# Pg16_PSU.net
KiCad netlist of a schematic drawn in Altium Designer
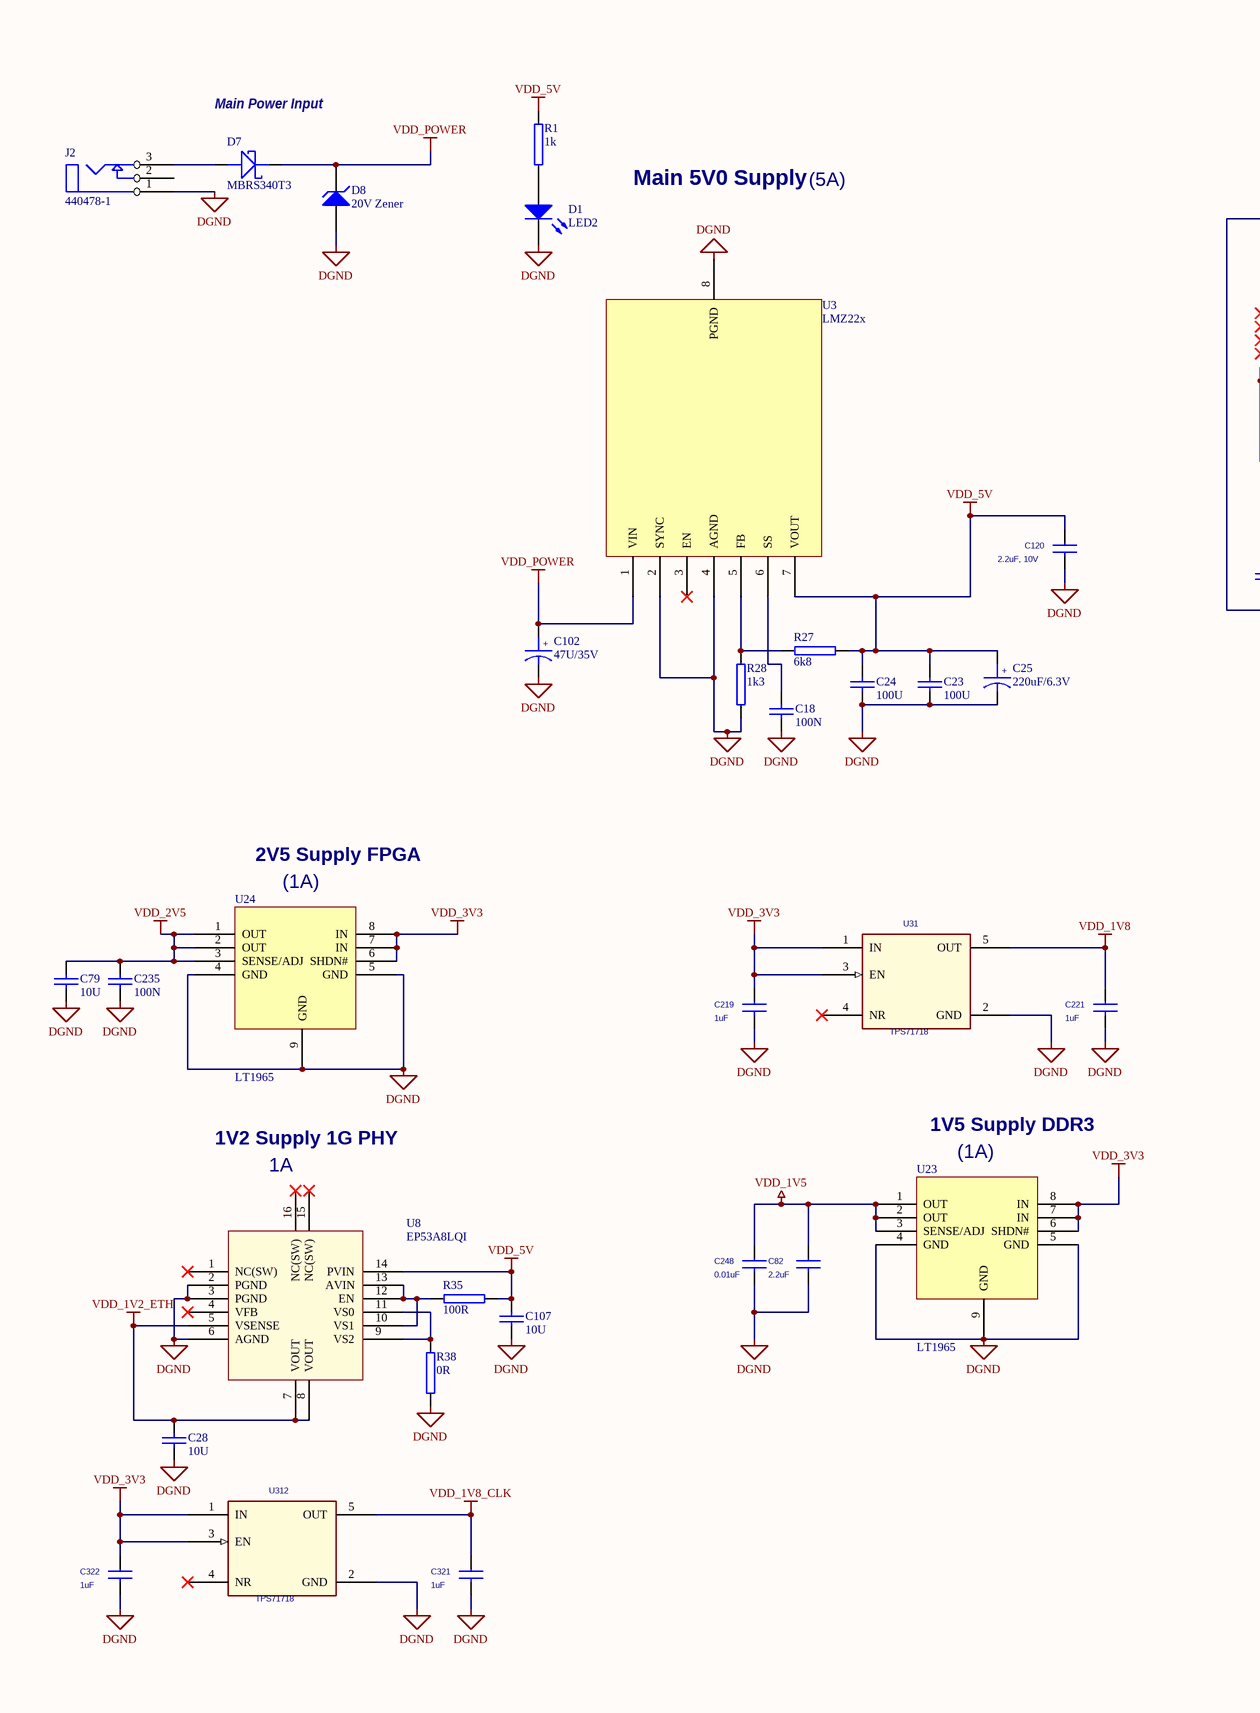
[diagram p0: Pg16_PSU.SchDoc, left]
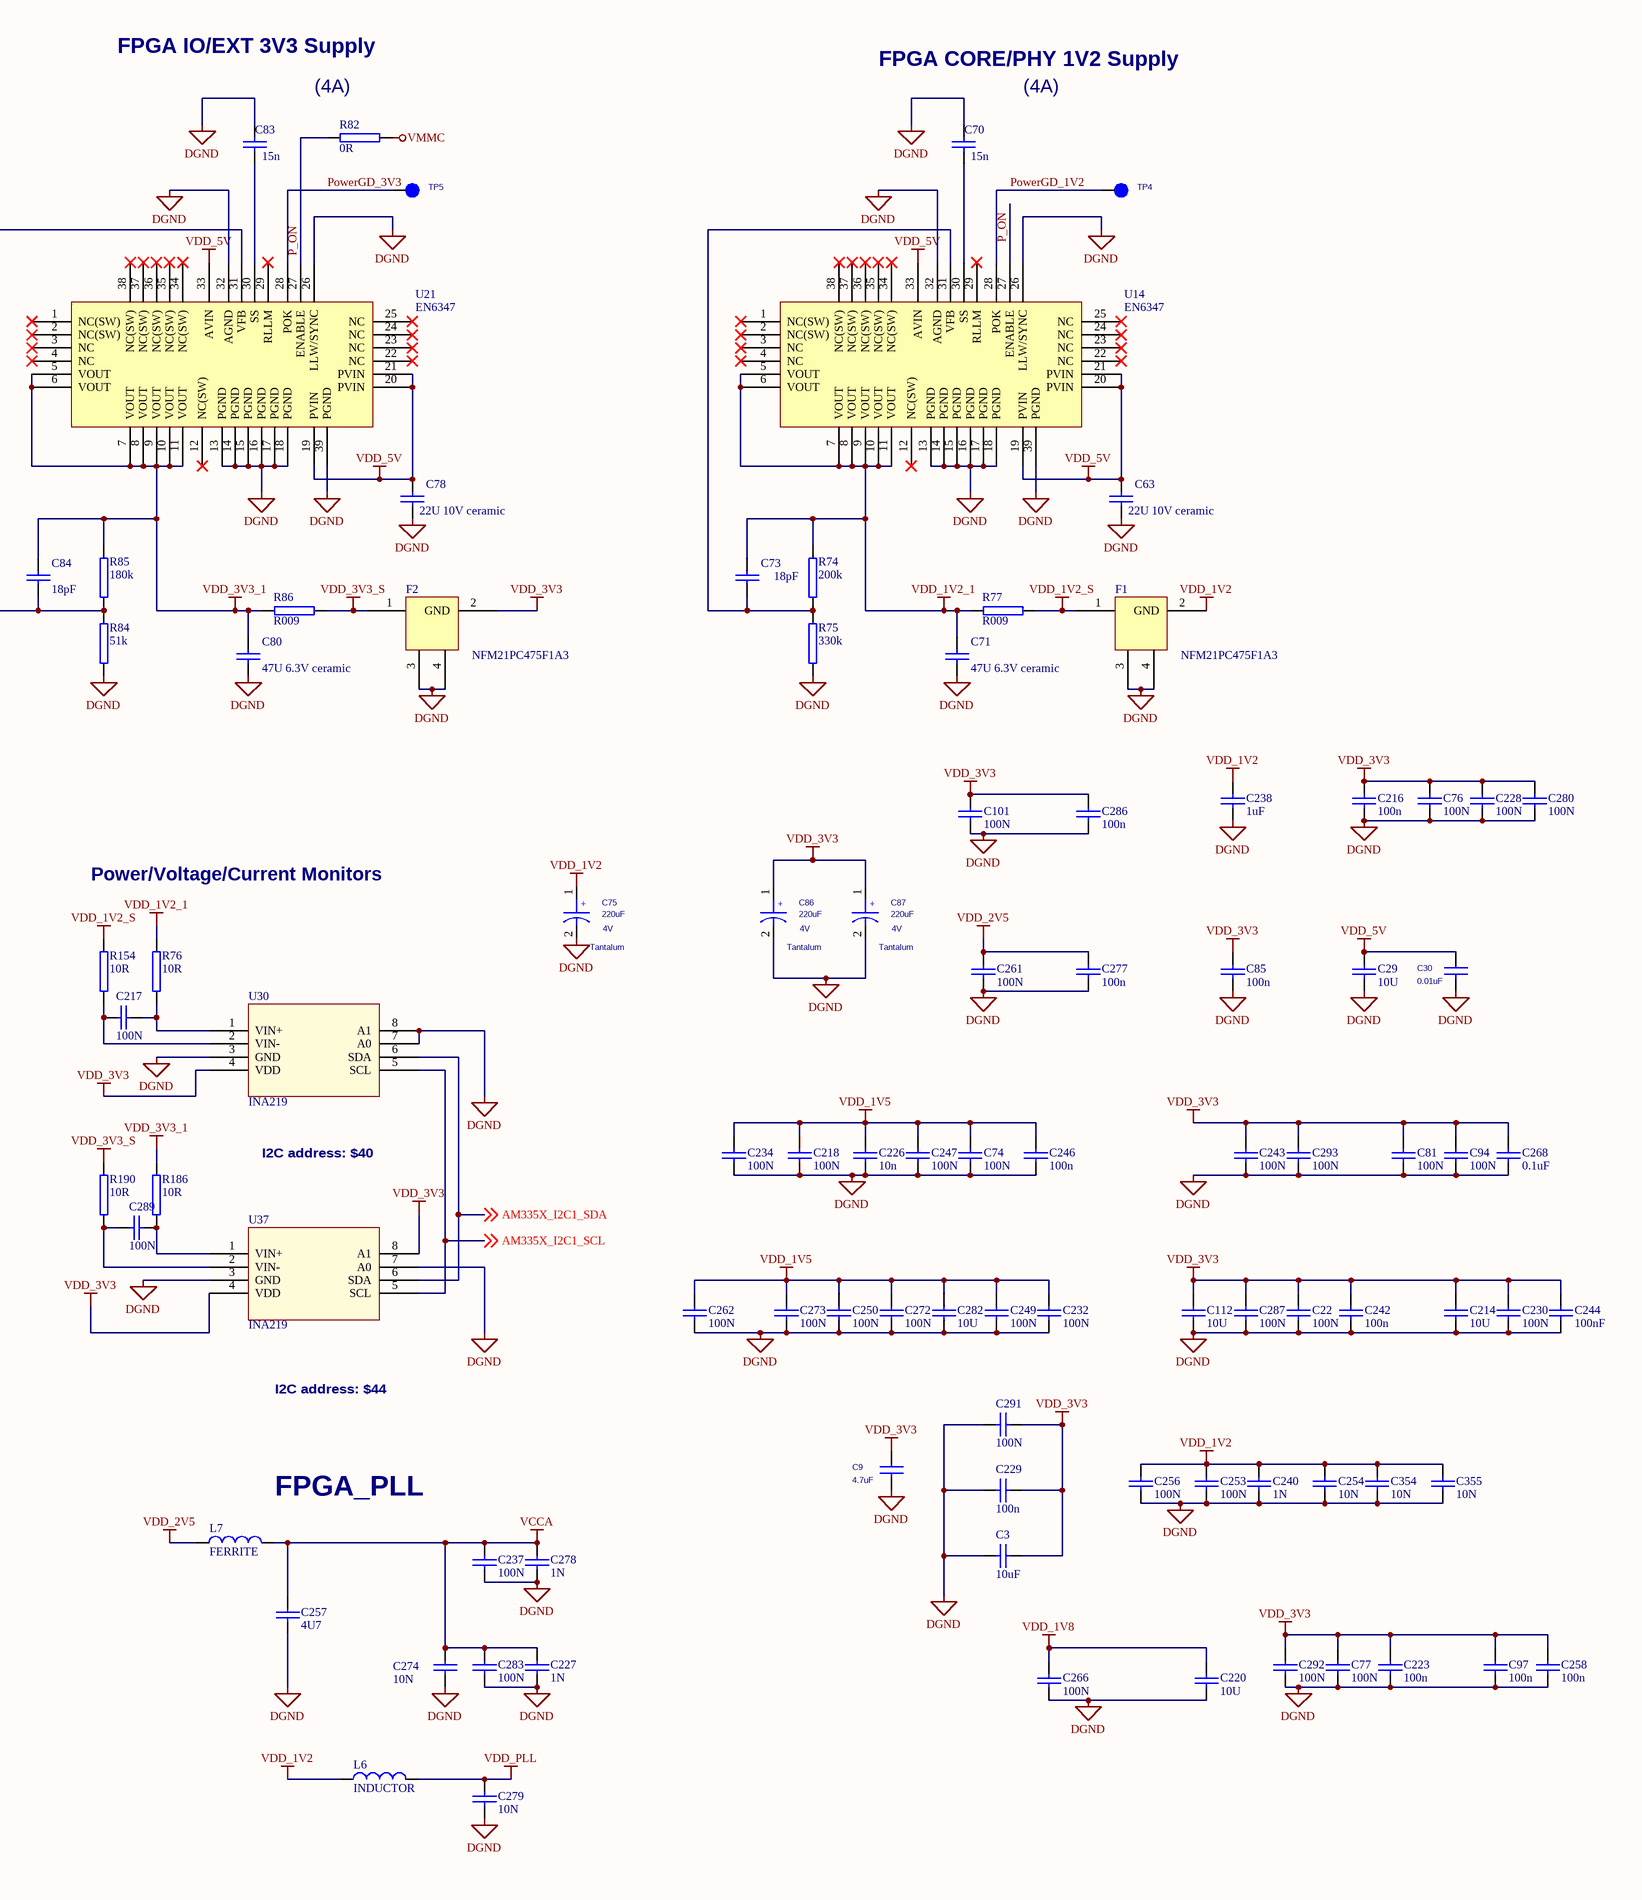
[diagram p1: Pg16_PSU.SchDoc, right]

(export (version "E")
  (design (tool "Eeschema 10.0.6"))
  (components
    (comp (ref "C3")
      (value "10uF")
      (footprint "SC0603")
      (description "NON-POLARISED CAP")
      (libsource (lib "Fireflash_B") (part "CAP"))
    )
    (comp (ref "C9")
      (value "4.7uF")
      (footprint "SM-7351-CAP-0603")
      (fields (field (name "TIINTPARTNUMBER") "1C0103") (field (name "MFR") "Taiyo Yuden"))
      (libsource (lib "*") (part "4.7uFCapacitor16V10%0603"))
    )
    (comp (ref "C18")
      (value "100N")
      (footprint "sc0402")
      (description "NON-POLARISED CAP")
      (libsource (lib "Fireflash_B") (part "CAP"))
    )
    (comp (ref "C22")
      (value "100N")
      (footprint "0603")
      (description "NON-POLARISED CAP")
      (libsource (lib "Fireflash_B") (part "CAP"))
    )
    (comp (ref "C23")
      (value "100U")
      (footprint "1206")
      (description "NON-POLARISED CAP")
      (libsource (lib "Fireflash_B") (part "CAP"))
    )
    (comp (ref "C24")
      (value "100U")
      (footprint "1206")
      (description "NON-POLARISED CAP")
      (libsource (lib "Fireflash_B") (part "CAP"))
    )
    (comp (ref "C25")
      (value "220uF/6.3V")
      (footprint "CASED")
      (description "POLARISED CAPACITOR")
      (libsource (lib "Fireflash_B") (part "CAP POL"))
    )
    (comp (ref "C28")
      (value "10U")
      (footprint "SC0603")
      (description "NON-POLARISED CAP")
      (libsource (lib "Fireflash_B") (part "CAP"))
    )
    (comp (ref "C29")
      (value "10U")
      (footprint "0805")
      (description "NON-POLARISED CAP")
      (libsource (lib "Fireflash_B") (part "CAP"))
    )
    (comp (ref "C30")
      (value "0.01uF")
      (footprint "SM-7351-CAP-0402")
      (fields (field (name "MFR") "Panasonic") (field (name "TIINTPARTNUMBER") "1C0012"))
      (libsource (lib "*") (part "0.01uFCapacitor16V10%0402_Dup1"))
    )
    (comp (ref "C63")
      (value "22U 10V ceramic")
      (footprint "1206")
      (description "NON-POLARISED CAP")
      (libsource (lib "*") (part "CAP"))
    )
    (comp (ref "C70")
      (value "15n")
      (footprint "sc0402")
      (description "NON-POLARISED CAP")
      (libsource (lib "*") (part "CAP"))
    )
    (comp (ref "C71")
      (value "47U 6.3V ceramic")
      (footprint "1206")
      (description "NON-POLARISED CAP")
      (libsource (lib "*") (part "CAP"))
    )
    (comp (ref "C73")
      (value "18pF")
      (footprint "sc0402")
      (description "NON-POLARISED CAP")
      (libsource (lib "*") (part "CAP"))
    )
    (comp (ref "C74")
      (value "100N")
      (footprint "0603")
      (description "NON-POLARISED CAP")
      (libsource (lib "Fireflash_B") (part "CAP"))
    )
    (comp (ref "C75")
      (value "220uF")
      (footprint "1210")
      (description "CAP - TANTALUM, 330UF, 10%, 4V, 700MOHM ESR, 6032-28")
      (fields
        (field (name "WORKING VOLTAGE") "4V")
        (field (name "DIELECTRIC") "Tantalum")
        (field (name "TOLERANCE") "+/-10%")
        (field (name "MANUFACTURER") "Kemet Corporation")
      )
      (libsource (lib "*") (part "CAP_SMD_POL"))
    )
    (comp (ref "C76")
      (value "100N")
      (footprint "sc0402")
      (description "NON-POLARISED CAP")
      (libsource (lib "Fireflash_B") (part "CAP"))
    )
    (comp (ref "C77")
      (value "100N")
      (footprint "0603")
      (description "NON-POLARISED CAP")
      (libsource (lib "Fireflash_B") (part "CAP"))
    )
    (comp (ref "C78")
      (value "22U 10V ceramic")
      (footprint "1206")
      (description "NON-POLARISED CAP")
      (libsource (lib "*") (part "CAP"))
    )
    (comp (ref "C79")
      (value "10U")
      (footprint "sc0603")
      (description "NON-POLARISED CAP")
      (libsource (lib "Fireflash_B") (part "CAP"))
    )
    (comp (ref "C80")
      (value "47U 6.3V ceramic")
      (footprint "1206")
      (description "NON-POLARISED CAP")
      (libsource (lib "*") (part "CAP"))
    )
    (comp (ref "C81")
      (value "100N")
      (footprint "0603")
      (description "NON-POLARISED CAP")
      (libsource (lib "Fireflash_B") (part "CAP"))
    )
    (comp (ref "C82")
      (value "2.2uF")
      (footprint "SM-7351-CAP-0805")
      (description "Capacitor 2.2uF 16V 10% 0805")
      (fields (field (name "TIINTPARTNUMBER") "1C0097") (field (name "MFR") "Kemet"))
      (libsource (lib "*") (part "2.2uF16V10%SMD0805"))
    )
    (comp (ref "C83")
      (value "15n")
      (footprint "sc0402")
      (description "NON-POLARISED CAP")
      (libsource (lib "*") (part "CAP"))
    )
    (comp (ref "C84")
      (value "18pF")
      (footprint "sc0402")
      (description "NON-POLARISED CAP")
      (libsource (lib "*") (part "CAP"))
    )
    (comp (ref "C85")
      (value "100n")
      (footprint "0603")
      (description "NON-POLARISED CAP")
      (libsource (lib "Fireflash_B") (part "CAP"))
    )
    (comp (ref "C86")
      (value "220uF")
      (footprint "1210")
      (description "CAP - TANTALUM, 330UF, 10%, 4V, 700MOHM ESR, 6032-28")
      (fields
        (field (name "WORKING VOLTAGE") "4V")
        (field (name "DIELECTRIC") "Tantalum")
        (field (name "TOLERANCE") "+/-10%")
        (field (name "MANUFACTURER") "Kemet Corporation")
      )
      (libsource (lib "*") (part "CAP_SMD_POL"))
    )
    (comp (ref "C87")
      (value "220uF")
      (footprint "1210")
      (description "CAP - TANTALUM, 330UF, 10%, 4V, 700MOHM ESR, 6032-28")
      (fields
        (field (name "WORKING VOLTAGE") "4V")
        (field (name "DIELECTRIC") "Tantalum")
        (field (name "TOLERANCE") "+/-10%")
        (field (name "MANUFACTURER") "Kemet Corporation")
      )
      (libsource (lib "*") (part "CAP_SMD_POL"))
    )
    (comp (ref "C94")
      (value "100N")
      (footprint "0603")
      (description "NON-POLARISED CAP")
      (libsource (lib "Fireflash_B") (part "CAP"))
    )
    (comp (ref "C97")
      (value "100n")
      (footprint "0603")
      (description "NON-POLARISED CAP")
      (libsource (lib "Fireflash_B") (part "CAP"))
    )
    (comp (ref "C101")
      (value "100N")
      (footprint "0603")
      (description "NON-POLARISED CAP")
      (libsource (lib "Fireflash_B") (part "CAP"))
    )
    (comp (ref "C102")
      (value "47U/35V")
      (footprint "CASED")
      (description "POLARISED CAPACITOR")
      (libsource (lib "Fireflash_B") (part "CAP POL"))
    )
    (comp (ref "C107")
      (value "10U")
      (footprint "SC0603")
      (description "NON-POLARISED CAP")
      (libsource (lib "Fireflash_B") (part "CAP"))
    )
    (comp (ref "C112")
      (value "10U")
      (footprint "SC0603")
      (description "NON-POLARISED CAP")
      (libsource (lib "Fireflash_B") (part "CAP"))
    )
    (comp (ref "C120")
      (value "2.2uF, 10V")
      (footprint "SM-7351-CAP-0402")
      (fields (field (name "TIINTPARTNUMBER") "1C0123") (field (name "MFR") "Taiyo Yuden"))
      (libsource (lib "*") (part "2.2uFCapacitor10V20%smd0402"))
    )
    (comp (ref "C214")
      (value "10U")
      (footprint "0603")
      (description "NON-POLARISED CAP")
      (libsource (lib "Fireflash_B") (part "CAP"))
    )
    (comp (ref "C216")
      (value "100n")
      (footprint "0603")
      (description "NON-POLARISED CAP")
      (libsource (lib "Fireflash_B") (part "CAP"))
    )
    (comp (ref "C217")
      (value "100N")
      (footprint "sc0402")
      (description "NON-POLARISED CAP")
      (libsource (lib "Fireflash_B") (part "CAP"))
    )
    (comp (ref "C218")
      (value "100N")
      (footprint "0603")
      (description "NON-POLARISED CAP")
      (libsource (lib "Fireflash_B") (part "CAP"))
    )
    (comp (ref "C219")
      (value "1uF")
      (footprint "SM-7351-CAP-0402")
      (fields (field (name "TIINTPARTNUMBER") "1C0084") (field (name "MFR") "AVX"))
      (libsource (lib "*") (part "1uFCapacitor10V10%0402"))
    )
    (comp (ref "C220")
      (value "10U")
      (footprint "sc0603")
      (description "NON-POLARISED CAP")
      (libsource (lib "Fireflash_B") (part "CAP"))
    )
    (comp (ref "C221")
      (value "1uF")
      (footprint "SM-7351-CAP-0402")
      (fields (field (name "TIINTPARTNUMBER") "1C0084") (field (name "MFR") "AVX"))
      (libsource (lib "*") (part "1uFCapacitor10V10%0402"))
    )
    (comp (ref "C223")
      (value "100n")
      (footprint "0603")
      (description "NON-POLARISED CAP")
      (libsource (lib "Fireflash_B") (part "CAP"))
    )
    (comp (ref "C226")
      (value "10n")
      (footprint "0603")
      (description "NON-POLARISED CAP")
      (libsource (lib "Fireflash_B") (part "CAP"))
    )
    (comp (ref "C227")
      (value "1N")
      (footprint "sc0402")
      (description "NON-POLARISED CAP")
      (libsource (lib "Fireflash_B") (part "CAP"))
    )
    (comp (ref "C228")
      (value "100N")
      (footprint "0603")
      (description "NON-POLARISED CAP")
      (libsource (lib "Fireflash_B") (part "CAP"))
    )
    (comp (ref "C229")
      (value "100n")
      (footprint "0603")
      (description "NON-POLARISED CAP")
      (libsource (lib "Fireflash_B") (part "CAP"))
    )
    (comp (ref "C230")
      (value "100N")
      (footprint "0603")
      (description "NON-POLARISED CAP")
      (libsource (lib "Fireflash_B") (part "CAP"))
    )
    (comp (ref "C232")
      (value "100N")
      (footprint "0603")
      (description "NON-POLARISED CAP")
      (libsource (lib "Fireflash_B") (part "CAP"))
    )
    (comp (ref "C234")
      (value "100N")
      (footprint "SM-7351-CAP-0402")
      (description "NON-POLARISED CAP")
      (libsource (lib "Fireflash_B") (part "CAP"))
    )
    (comp (ref "C235")
      (value "100N")
      (footprint "sc0402")
      (description "NON-POLARISED CAP")
      (libsource (lib "Fireflash_B") (part "CAP"))
    )
    (comp (ref "C237")
      (value "100N")
      (footprint "sc0402")
      (description "NON-POLARISED CAP")
      (libsource (lib "Fireflash_B") (part "CAP"))
    )
    (comp (ref "C238")
      (value "1uF")
      (footprint "sc0402")
      (description "NON-POLARISED CAP")
      (libsource (lib "Fireflash_B") (part "CAP"))
    )
    (comp (ref "C240")
      (value "1N")
      (footprint "SM-7351-CAP-0402")
      (description "NON-POLARISED CAP")
      (libsource (lib "Fireflash_B") (part "CAP"))
    )
    (comp (ref "C242")
      (value "100n")
      (footprint "0603")
      (description "NON-POLARISED CAP")
      (libsource (lib "Fireflash_B") (part "CAP"))
    )
    (comp (ref "C243")
      (value "100N")
      (footprint "0603")
      (description "NON-POLARISED CAP")
      (libsource (lib "Fireflash_B") (part "CAP"))
    )
    (comp (ref "C244")
      (value "100nF")
      (footprint "0603")
      (description "NON-POLARISED CAP")
      (libsource (lib "Fireflash_B") (part "CAP"))
    )
    (comp (ref "C246")
      (value "100n")
      (footprint "SM-7351-CAP-0402")
      (description "NON-POLARISED CAP")
      (libsource (lib "Fireflash_B") (part "CAP"))
    )
    (comp (ref "C247")
      (value "100N")
      (footprint "SM-7351-CAP-0402")
      (description "NON-POLARISED CAP")
      (libsource (lib "Fireflash_B") (part "CAP"))
    )
    (comp (ref "C248")
      (value "0.01uF")
      (footprint "SM-7351-CAP-0402")
      (fields (field (name "MFR") "Panasonic") (field (name "TIINTPARTNUMBER") "1C0012"))
      (libsource (lib "*") (part "0.01uFCapacitor16V10%0402_Dup1"))
    )
    (comp (ref "C249")
      (value "100N")
      (footprint "0603")
      (description "NON-POLARISED CAP")
      (libsource (lib "Fireflash_B") (part "CAP"))
    )
    (comp (ref "C250")
      (value "100N")
      (footprint "0603")
      (description "NON-POLARISED CAP")
      (libsource (lib "Fireflash_B") (part "CAP"))
    )
    (comp (ref "C253")
      (value "100N")
      (footprint "SM-7351-CAP-0402")
      (description "NON-POLARISED CAP")
      (libsource (lib "Fireflash_B") (part "CAP"))
    )
    (comp (ref "C254")
      (value "10N")
      (footprint "SM-7351-CAP-0402")
      (description "NON-POLARISED CAP")
      (libsource (lib "Fireflash_B") (part "CAP"))
    )
    (comp (ref "C256")
      (value "100N")
      (footprint "SM-7351-CAP-0402")
      (description "NON-POLARISED CAP")
      (libsource (lib "Fireflash_B") (part "CAP"))
    )
    (comp (ref "C257")
      (value "4U7")
      (footprint "0603")
      (description "NON-POLARISED CAP")
      (libsource (lib "Fireflash_B") (part "CAP"))
    )
    (comp (ref "C258")
      (value "100n")
      (footprint "0603")
      (description "NON-POLARISED CAP")
      (libsource (lib "Fireflash_B") (part "CAP"))
    )
    (comp (ref "C261")
      (value "100N")
      (footprint "sc0402")
      (description "NON-POLARISED CAP")
      (libsource (lib "Fireflash_B") (part "CAP"))
    )
    (comp (ref "C262")
      (value "100N")
      (footprint "sc0402")
      (description "NON-POLARISED CAP")
      (libsource (lib "Fireflash_B") (part "CAP"))
    )
    (comp (ref "C266")
      (value "100N")
      (footprint "sc0402")
      (description "NON-POLARISED CAP")
      (libsource (lib "Fireflash_B") (part "CAP"))
    )
    (comp (ref "C268")
      (value "0.1uF")
      (footprint "sc0402")
      (description "NON-POLARISED CAP")
      (libsource (lib "Fireflash_B") (part "CAP"))
    )
    (comp (ref "C272")
      (value "100N")
      (footprint "0603")
      (description "NON-POLARISED CAP")
      (libsource (lib "Fireflash_B") (part "CAP"))
    )
    (comp (ref "C273")
      (value "100N")
      (footprint "sc0402")
      (description "NON-POLARISED CAP")
      (libsource (lib "Fireflash_B") (part "CAP"))
    )
    (comp (ref "C274")
      (value "10N")
      (footprint "SC0603")
      (description "NON-POLARISED CAP")
      (libsource (lib "Fireflash_B") (part "CAP"))
    )
    (comp (ref "C277")
      (value "100n")
      (footprint "0603")
      (description "NON-POLARISED CAP")
      (libsource (lib "Fireflash_B") (part "CAP"))
    )
    (comp (ref "C278")
      (value "1N")
      (footprint "sc0402")
      (description "NON-POLARISED CAP")
      (libsource (lib "Fireflash_B") (part "CAP"))
    )
    (comp (ref "C279")
      (value "10N")
      (footprint "SM-7351-CAP-0402")
      (description "NON-POLARISED CAP")
      (libsource (lib "Fireflash_B") (part "CAP"))
    )
    (comp (ref "C280")
      (value "100N")
      (footprint "0603")
      (description "NON-POLARISED CAP")
      (libsource (lib "Fireflash_B") (part "CAP"))
    )
    (comp (ref "C282")
      (value "10U")
      (footprint "sc0603")
      (description "NON-POLARISED CAP")
      (libsource (lib "Fireflash_B") (part "CAP"))
    )
    (comp (ref "C283")
      (value "100N")
      (footprint "sc0402")
      (description "NON-POLARISED CAP")
      (libsource (lib "Fireflash_B") (part "CAP"))
    )
    (comp (ref "C286")
      (value "100n")
      (footprint "0603")
      (description "NON-POLARISED CAP")
      (libsource (lib "Fireflash_B") (part "CAP"))
    )
    (comp (ref "C287")
      (value "100N")
      (footprint "0603")
      (description "NON-POLARISED CAP")
      (libsource (lib "Fireflash_B") (part "CAP"))
    )
    (comp (ref "C289")
      (value "100N")
      (footprint "sc0402")
      (description "NON-POLARISED CAP")
      (libsource (lib "Fireflash_B") (part "CAP"))
    )
    (comp (ref "C291")
      (value "100N")
      (footprint "sc0402")
      (description "NON-POLARISED CAP")
      (libsource (lib "Fireflash_B") (part "CAP"))
    )
    (comp (ref "C292")
      (value "100N")
      (footprint "0603")
      (description "NON-POLARISED CAP")
      (libsource (lib "Fireflash_B") (part "CAP"))
    )
    (comp (ref "C293")
      (value "100N")
      (footprint "0603")
      (description "NON-POLARISED CAP")
      (libsource (lib "Fireflash_B") (part "CAP"))
    )
    (comp (ref "C321")
      (value "1uF")
      (footprint "SM-7351-CAP-0402")
      (fields (field (name "TIINTPARTNUMBER") "1C0084") (field (name "MFR") "AVX"))
      (libsource (lib "*") (part "1uFCapacitor10V10%0402"))
    )
    (comp (ref "C322")
      (value "1uF")
      (footprint "SM-7351-CAP-0402")
      (fields (field (name "TIINTPARTNUMBER") "1C0084") (field (name "MFR") "AVX"))
      (libsource (lib "*") (part "1uFCapacitor10V10%0402"))
    )
    (comp (ref "C354")
      (value "10N")
      (footprint "SM-7351-CAP-0402")
      (description "NON-POLARISED CAP")
      (libsource (lib "Fireflash_B") (part "CAP"))
    )
    (comp (ref "C355")
      (value "10N")
      (footprint "SM-7351-CAP-0402")
      (description "NON-POLARISED CAP")
      (libsource (lib "Fireflash_B") (part "CAP"))
    )
    (comp (ref "D1")
      (value "LED2")
      (footprint "0603")
      (description "Typical RED, GREEN, YELLOW, AMBER GaAs LED")
      (fields (field (name "PUBLISHER") "Altium Limited"))
      (libsource (lib "Miscellaneous Devices") (part "LED2"))
    )
    (comp (ref "D7")
      (value "MBRS340T3")
      (footprint "SMC")
      (description "SCHOTTKY DIODE")
      (libsource (lib "Fireflash_B") (part "MBRS340T3"))
    )
    (comp (ref "D8")
      (value "20V Zener")
      (footprint "SMB")
      (description "Zener Diode")
      (fields (field (name "PUBLISHER") "Altium Limited"))
      (libsource (lib "Miscellaneous Devices") (part "D Zener"))
    )
    (comp (ref "F1")
      (value "NFM21PC475F1A3")
      (footprint "EM chip filter 0805")
      (description "3 terminal feedthough filter capacitor")
      (libsource (lib "Ibis4") (part "NFM41PC204F1H3"))
    )
    (comp (ref "F2")
      (value "NFM21PC475F1A3")
      (footprint "EM chip filter 0805")
      (description "3 terminal feedthough filter capacitor")
      (libsource (lib "Ibis4") (part "NFM41PC204F1H3"))
    )
    (comp (ref "J2")
      (value "440478-1")
      (footprint "CON_POWER")
      (description "2.1mm power connector")
      (libsource (lib "Fireflash_B") (part "CON_POWER"))
    )
    (comp (ref "L6")
      (value "INDUCTOR")
      (footprint "sc0603")
      (libsource (lib "Fireflash_B") (part "INDUCTOR"))
    )
    (comp (ref "L7")
      (value "FERRITE")
      (footprint "SC0603")
      (description "INDUCTOR")
      (libsource (lib "Fireflash_B") (part "INDUCTOR"))
    )
    (comp (ref "R1")
      (value "1k")
      (footprint "0603")
      (description "RESISTOR")
      (libsource (lib "Fireflash_B") (part "RES"))
    )
    (comp (ref "R27")
      (value "6k8")
      (footprint "sc0402")
      (description "RESISTOR")
      (libsource (lib "Fireflash_B") (part "RES"))
    )
    (comp (ref "R28")
      (value "1k3")
      (footprint "sc0402")
      (description "RESISTOR")
      (libsource (lib "Fireflash_B") (part "RES"))
    )
    (comp (ref "R35")
      (value "100R")
      (footprint "sc0402")
      (description "RESISTOR")
      (libsource (lib "*") (part "RES"))
    )
    (comp (ref "R38")
      (value "0R")
      (footprint "sc0402")
      (description "RESISTOR")
      (libsource (lib "*") (part "RES"))
    )
    (comp (ref "R74")
      (value "200k")
      (footprint "sc0402")
      (description "RESISTOR")
      (libsource (lib "*") (part "RES"))
    )
    (comp (ref "R75")
      (value "330k")
      (footprint "sc0402")
      (description "RESISTOR")
      (libsource (lib "*") (part "RES"))
    )
    (comp (ref "R76")
      (value "10R")
      (footprint "sc0402")
      (description "RESISTOR")
      (libsource (lib "Fireflash_B") (part "RES"))
    )
    (comp (ref "R77")
      (value "R009")
      (footprint "1206")
      (description "Resistor")
      (libsource (lib "Ibis4") (part "RES"))
    )
    (comp (ref "R82")
      (value "0R")
      (footprint "sc0402")
      (description "RESISTOR")
      (libsource (lib "") (part "RES_1"))
    )
    (comp (ref "R84")
      (value "51k")
      (footprint "sc0402")
      (description "RESISTOR")
      (libsource (lib "*") (part "RES"))
    )
    (comp (ref "R85")
      (value "180k")
      (footprint "sc0402")
      (description "RESISTOR")
      (libsource (lib "*") (part "RES"))
    )
    (comp (ref "R86")
      (value "R009")
      (footprint "1206")
      (description "Resistor")
      (libsource (lib "Ibis4") (part "RES"))
    )
    (comp (ref "R154")
      (value "10R")
      (footprint "sc0402")
      (description "RESISTOR")
      (libsource (lib "Fireflash_B") (part "RES"))
    )
    (comp (ref "R186")
      (value "10R")
      (footprint "sc0402")
      (description "RESISTOR")
      (libsource (lib "Fireflash_B") (part "RES"))
    )
    (comp (ref "R190")
      (value "10R")
      (footprint "sc0402")
      (description "RESISTOR")
      (libsource (lib "Fireflash_B") (part "RES"))
    )
    (comp (ref "TP4")
      (value "TP1mm")
      (footprint "tp_smd1mmcircle")
      (description "Testpoint SMD 1mm circle pad")
      (fields (field (name "TIINTPARTNUMBER") "2H0046"))
      (libsource (lib "*") (part "Testpoint_SMD1mmCircle"))
    )
    (comp (ref "TP5")
      (value "TP1mm")
      (footprint "tp_smd1mmcircle")
      (description "Testpoint SMD 1mm circle pad")
      (fields (field (name "TIINTPARTNUMBER") "2H0046"))
      (libsource (lib "*") (part "Testpoint_SMD1mmCircle"))
    )
    (comp (ref "U3")
      (value "LMZ22x")
      (footprint "TZA07A")
      (description "Power Module")
      (libsource (lib "Fireflash_B") (part "LMZ22x"))
    )
    (comp (ref "U8")
      (value "EP53A8LQI")
      (footprint "LCC 16pin 3x3 mm")
      (libsource (lib "testlib") (part "EP53A8xQI"))
    )
    (comp (ref "U14")
      (value "EN6347")
      (footprint "EN6347QI - DFN")
      (description "4A PSU power module")
      (libsource (lib "Fireflash_B") (part "EN6347QI"))
    )
    (comp (ref "U21")
      (value "EN6347")
      (footprint "EN6347QI - DFN")
      (description "4A PSU power module")
      (libsource (lib "Fireflash_B") (part "EN6347QI"))
    )
    (comp (ref "U23")
      (value "LT1965")
      (footprint "DD package")
      (description "LDO regulator adjustable")
      (libsource (lib "ARMflash1a") (part "LT1965"))
    )
    (comp (ref "U24")
      (value "LT1965")
      (footprint "DD package")
      (description "LDO regulator adjustable")
      (libsource (lib "ARMflash1a") (part "LT1965"))
    )
    (comp (ref "U30")
      (value "INA219")
      (footprint "SOT23-8")
      (description "Current/Power Monitor I2C")
      (libsource (lib "Medipix3") (part "INA219"))
    )
    (comp (ref "U31")
      (value "TPS71718")
      (footprint "smdsc70-5")
      (description "Low Dropout 1.8V 150mA Linear Regulator")
      (fields (field (name "MFR") "TI") (field (name "TIINTPARTNUMBER") "1A0262"))
      (libsource (lib "*") (part "TPS71718"))
    )
    (comp (ref "U37")
      (value "INA219")
      (footprint "SOT23-8")
      (description "Current/Power Monitor I2C")
      (libsource (lib "Medipix3") (part "INA219"))
    )
    (comp (ref "U312")
      (value "TPS71718")
      (footprint "smdsc70-5")
      (description "Low Dropout 1.8V 150mA Linear Regulator")
      (fields (field (name "MFR") "TI") (field (name "TIINTPARTNUMBER") "1A0262"))
      (libsource (lib "*") (part "TPS71718"))
    )
  )
  (nets
    (net (code "1") (name "/P_ON") (class "Default")
      (node (ref "R82") (pin "2") (pintype "passive"))
      (node (ref "U14") (pin "27") (pinfunction "ENABLE_27") (pintype "passive"))
      (node (ref "U21") (pin "27") (pinfunction "ENABLE_27") (pintype "passive"))
    )
    (net (code "2") (name "/PowerGD_1V2") (class "Default")
      (node (ref "TP4") (pin "1") (pinfunction "1_1") (pintype "passive"))
      (node (ref "U14") (pin "28") (pinfunction "POK_28") (pintype "passive"))
    )
    (net (code "3") (name "/PowerGD_3V3") (class "Default")
      (node (ref "TP5") (pin "1") (pinfunction "1_1") (pintype "passive"))
      (node (ref "U21") (pin "28") (pinfunction "POK_28") (pintype "passive"))
    )
    (net (code "4") (name "AM335X_I2C1_SCL") (class "Default")
      (node (ref "U30") (pin "5") (pinfunction "SCL_5") (pintype "passive"))
      (node (ref "U37") (pin "5") (pinfunction "SCL_5") (pintype "passive"))
    )
    (net (code "5") (name "AM335X_I2C1_SDA") (class "Default")
      (node (ref "U30") (pin "6") (pinfunction "SDA_6") (pintype "passive"))
      (node (ref "U37") (pin "6") (pinfunction "SDA_6") (pintype "passive"))
    )
    (net (code "6") (name "DGND") (class "Default")
      (node (ref "C101") (pin "2") (pintype "passive"))
      (node (ref "C102") (pin "2") (pinfunction "2_2") (pintype "passive"))
      (node (ref "C107") (pin "2") (pintype "passive"))
      (node (ref "C112") (pin "2") (pintype "passive"))
      (node (ref "C120") (pin "2") (pinfunction "2_2") (pintype "passive"))
      (node (ref "C18") (pin "2") (pintype "passive"))
      (node (ref "C214") (pin "2") (pintype "passive"))
      (node (ref "C216") (pin "2") (pintype "passive"))
      (node (ref "C218") (pin "2") (pintype "passive"))
      (node (ref "C219") (pin "2") (pinfunction "2_2") (pintype "passive"))
      (node (ref "C22") (pin "2") (pintype "passive"))
      (node (ref "C220") (pin "2") (pintype "passive"))
      (node (ref "C221") (pin "2") (pinfunction "2_2") (pintype "passive"))
      (node (ref "C223") (pin "2") (pintype "passive"))
      (node (ref "C226") (pin "2") (pintype "passive"))
      (node (ref "C227") (pin "2") (pintype "passive"))
      (node (ref "C228") (pin "2") (pintype "passive"))
      (node (ref "C229") (pin "1") (pintype "passive"))
      (node (ref "C23") (pin "2") (pintype "passive"))
      (node (ref "C230") (pin "2") (pintype "passive"))
      (node (ref "C232") (pin "2") (pintype "passive"))
      (node (ref "C234") (pin "2") (pintype "passive"))
      (node (ref "C235") (pin "2") (pintype "passive"))
      (node (ref "C237") (pin "2") (pintype "passive"))
      (node (ref "C238") (pin "2") (pintype "passive"))
      (node (ref "C24") (pin "2") (pintype "passive"))
      (node (ref "C240") (pin "2") (pintype "passive"))
      (node (ref "C242") (pin "2") (pintype "passive"))
      (node (ref "C243") (pin "2") (pintype "passive"))
      (node (ref "C244") (pin "2") (pintype "passive"))
      (node (ref "C246") (pin "2") (pintype "passive"))
      (node (ref "C247") (pin "2") (pintype "passive"))
      (node (ref "C248") (pin "2") (pinfunction "2_2") (pintype "passive"))
      (node (ref "C249") (pin "2") (pintype "passive"))
      (node (ref "C25") (pin "2") (pinfunction "2_2") (pintype "passive"))
      (node (ref "C250") (pin "2") (pintype "passive"))
      (node (ref "C253") (pin "2") (pintype "passive"))
      (node (ref "C254") (pin "2") (pintype "passive"))
      (node (ref "C256") (pin "2") (pintype "passive"))
      (node (ref "C257") (pin "2") (pintype "passive"))
      (node (ref "C258") (pin "2") (pintype "passive"))
      (node (ref "C261") (pin "2") (pintype "passive"))
      (node (ref "C262") (pin "2") (pintype "passive"))
      (node (ref "C266") (pin "2") (pintype "passive"))
      (node (ref "C268") (pin "2") (pintype "passive"))
      (node (ref "C272") (pin "2") (pintype "passive"))
      (node (ref "C273") (pin "2") (pintype "passive"))
      (node (ref "C274") (pin "1") (pintype "passive"))
      (node (ref "C277") (pin "2") (pintype "passive"))
      (node (ref "C278") (pin "2") (pintype "passive"))
      (node (ref "C279") (pin "1") (pintype "passive"))
      (node (ref "C28") (pin "2") (pintype "passive"))
      (node (ref "C280") (pin "2") (pintype "passive"))
      (node (ref "C282") (pin "2") (pintype "passive"))
      (node (ref "C283") (pin "2") (pintype "passive"))
      (node (ref "C286") (pin "2") (pintype "passive"))
      (node (ref "C287") (pin "2") (pintype "passive"))
      (node (ref "C29") (pin "2") (pintype "passive"))
      (node (ref "C291") (pin "1") (pintype "passive"))
      (node (ref "C292") (pin "2") (pintype "passive"))
      (node (ref "C293") (pin "2") (pintype "passive"))
      (node (ref "C3") (pin "1") (pintype "passive"))
      (node (ref "C30") (pin "2") (pinfunction "2_2") (pintype "passive"))
      (node (ref "C321") (pin "2") (pinfunction "2_2") (pintype "passive"))
      (node (ref "C322") (pin "2") (pinfunction "2_2") (pintype "passive"))
      (node (ref "C354") (pin "2") (pintype "passive"))
      (node (ref "C355") (pin "2") (pintype "passive"))
      (node (ref "C63") (pin "1") (pintype "passive"))
      (node (ref "C70") (pin "1") (pintype "passive"))
      (node (ref "C71") (pin "1") (pintype "passive"))
      (node (ref "C74") (pin "2") (pintype "passive"))
      (node (ref "C75") (pin "2") (pinfunction "2_2") (pintype "passive"))
      (node (ref "C76") (pin "2") (pintype "passive"))
      (node (ref "C77") (pin "2") (pintype "passive"))
      (node (ref "C78") (pin "1") (pintype "passive"))
      (node (ref "C79") (pin "2") (pintype "passive"))
      (node (ref "C80") (pin "1") (pintype "passive"))
      (node (ref "C81") (pin "2") (pintype "passive"))
      (node (ref "C82") (pin "2") (pinfunction "2_2") (pintype "passive"))
      (node (ref "C83") (pin "1") (pintype "passive"))
      (node (ref "C85") (pin "2") (pintype "passive"))
      (node (ref "C86") (pin "2") (pinfunction "2_2") (pintype "passive"))
      (node (ref "C87") (pin "2") (pinfunction "2_2") (pintype "passive"))
      (node (ref "C9") (pin "2") (pinfunction "2_2") (pintype "passive"))
      (node (ref "C94") (pin "2") (pintype "passive"))
      (node (ref "C97") (pin "2") (pintype "passive"))
      (node (ref "D1") (pin "2") (pinfunction "K_2") (pintype "passive"))
      (node (ref "D8") (pin "1") (pinfunction "A_1") (pintype "passive"))
      (node (ref "F1") (pin "3") (pinfunction "3_3") (pintype "passive"))
      (node (ref "F1") (pin "4") (pinfunction "4_4") (pintype "passive"))
      (node (ref "F2") (pin "3") (pinfunction "3_3") (pintype "passive"))
      (node (ref "F2") (pin "4") (pinfunction "4_4") (pintype "passive"))
      (node (ref "J2") (pin "1") (pinfunction "1_1") (pintype "passive"))
      (node (ref "R28") (pin "2") (pintype "passive"))
      (node (ref "R38") (pin "2") (pintype "passive"))
      (node (ref "R75") (pin "1") (pintype "passive"))
      (node (ref "R84") (pin "1") (pintype "passive"))
      (node (ref "U14") (pin "13") (pinfunction "PGND_13") (pintype "passive"))
      (node (ref "U14") (pin "14") (pinfunction "PGND_14") (pintype "passive"))
      (node (ref "U14") (pin "15") (pinfunction "PGND_15") (pintype "passive"))
      (node (ref "U14") (pin "16") (pinfunction "PGND_16") (pintype "passive"))
      (node (ref "U14") (pin "17") (pinfunction "PGND_17") (pintype "passive"))
      (node (ref "U14") (pin "18") (pinfunction "PGND_18") (pintype "passive"))
      (node (ref "U14") (pin "26") (pinfunction "LLW/SYNC_26") (pintype "passive"))
      (node (ref "U14") (pin "32") (pinfunction "AGND_32") (pintype "passive"))
      (node (ref "U14") (pin "39") (pinfunction "PGND_39") (pintype "passive"))
      (node (ref "U21") (pin "13") (pinfunction "PGND_13") (pintype "passive"))
      (node (ref "U21") (pin "14") (pinfunction "PGND_14") (pintype "passive"))
      (node (ref "U21") (pin "15") (pinfunction "PGND_15") (pintype "passive"))
      (node (ref "U21") (pin "16") (pinfunction "PGND_16") (pintype "passive"))
      (node (ref "U21") (pin "17") (pinfunction "PGND_17") (pintype "passive"))
      (node (ref "U21") (pin "18") (pinfunction "PGND_18") (pintype "passive"))
      (node (ref "U21") (pin "26") (pinfunction "LLW/SYNC_26") (pintype "passive"))
      (node (ref "U21") (pin "32") (pinfunction "AGND_32") (pintype "passive"))
      (node (ref "U21") (pin "39") (pinfunction "PGND_39") (pintype "passive"))
      (node (ref "U23") (pin "4") (pinfunction "GND_4") (pintype "passive"))
      (node (ref "U23") (pin "5") (pinfunction "GND_5") (pintype "passive"))
      (node (ref "U23") (pin "9") (pinfunction "GND_9") (pintype "passive"))
      (node (ref "U24") (pin "4") (pinfunction "GND_4") (pintype "passive"))
      (node (ref "U24") (pin "5") (pinfunction "GND_5") (pintype "passive"))
      (node (ref "U24") (pin "9") (pinfunction "GND_9") (pintype "passive"))
      (node (ref "U3") (pin "2") (pinfunction "SYNC_2") (pintype "passive"))
      (node (ref "U3") (pin "4") (pinfunction "AGND_4") (pintype "passive"))
      (node (ref "U3") (pin "8") (pinfunction "PGND_8") (pintype "passive"))
      (node (ref "U30") (pin "3") (pinfunction "GND_3") (pintype "passive"))
      (node (ref "U30") (pin "7") (pinfunction "A0_7") (pintype "passive"))
      (node (ref "U30") (pin "8") (pinfunction "A1_8") (pintype "passive"))
      (node (ref "U31") (pin "2") (pinfunction "GND_2") (pintype "power_in"))
      (node (ref "U312") (pin "2") (pinfunction "GND_2") (pintype "power_in"))
      (node (ref "U37") (pin "3") (pinfunction "GND_3") (pintype "passive"))
      (node (ref "U37") (pin "7") (pinfunction "A0_7") (pintype "passive"))
      (node (ref "U8") (pin "2") (pinfunction "PGND_2") (pintype "passive"))
      (node (ref "U8") (pin "3") (pinfunction "PGND_3") (pintype "passive"))
      (node (ref "U8") (pin "6") (pinfunction "AGND_6") (pintype "passive"))
    )
    (net (code "7") (name "Net-(D1-A)") (class "Default")
      (node (ref "D1") (pin "1") (pinfunction "A_1") (pintype "passive"))
      (node (ref "R1") (pin "1") (pintype "passive"))
    )
    (net (code "8") (name "Net-(D7-ANODE)") (class "Default")
      (node (ref "D7") (pin "1") (pinfunction "ANODE_1") (pintype "passive"))
      (node (ref "J2") (pin "3") (pinfunction "3_3") (pintype "passive"))
    )
    (net (code "9") (name "Net-(U3-FB)") (class "Default")
      (node (ref "R27") (pin "2") (pintype "passive"))
      (node (ref "R28") (pin "1") (pintype "passive"))
      (node (ref "U3") (pin "5") (pinfunction "FB_5") (pintype "passive"))
    )
    (net (code "10") (name "Net-(U3-SS)") (class "Default")
      (node (ref "C18") (pin "1") (pintype "passive"))
      (node (ref "U3") (pin "6") (pinfunction "SS_6") (pintype "passive"))
    )
    (net (code "11") (name "Net-(U8-AVIN)") (class "Default")
      (node (ref "R35") (pin "2") (pintype "passive"))
      (node (ref "U8") (pin "10") (pinfunction "VS1_10") (pintype "passive"))
      (node (ref "U8") (pin "12") (pinfunction "EN_12") (pintype "passive"))
      (node (ref "U8") (pin "13") (pinfunction "AVIN_13") (pintype "passive"))
    )
    (net (code "12") (name "Net-(U8-VS0)") (class "Default")
      (node (ref "R38") (pin "1") (pintype "passive"))
      (node (ref "U8") (pin "11") (pinfunction "VS0_11") (pintype "passive"))
      (node (ref "U8") (pin "9") (pinfunction "VS2_9") (pintype "passive"))
    )
    (net (code "13") (name "Net-(U14-SS)") (class "Default")
      (node (ref "C70") (pin "2") (pintype "passive"))
      (node (ref "U14") (pin "30") (pinfunction "SS_30") (pintype "passive"))
    )
    (net (code "14") (name "Net-(U14-VFB)") (class "Default")
      (node (ref "C73") (pin "2") (pintype "passive"))
      (node (ref "R74") (pin "1") (pintype "passive"))
      (node (ref "R75") (pin "2") (pintype "passive"))
      (node (ref "U14") (pin "31") (pinfunction "VFB_31") (pintype "passive"))
    )
    (net (code "15") (name "Net-(U21-SS)") (class "Default")
      (node (ref "C83") (pin "2") (pintype "passive"))
      (node (ref "U21") (pin "30") (pinfunction "SS_30") (pintype "passive"))
    )
    (net (code "16") (name "Net-(U21-VFB)") (class "Default")
      (node (ref "C84") (pin "2") (pintype "passive"))
      (node (ref "R84") (pin "2") (pintype "passive"))
      (node (ref "R85") (pin "1") (pintype "passive"))
      (node (ref "U21") (pin "31") (pinfunction "VFB_31") (pintype "passive"))
    )
    (net (code "17") (name "Net-(U30-VIN+)") (class "Default")
      (node (ref "C217") (pin "2") (pintype "passive"))
      (node (ref "R76") (pin "2") (pintype "passive"))
      (node (ref "U30") (pin "1") (pinfunction "VIN+_1") (pintype "passive"))
    )
    (net (code "18") (name "Net-(U30-VIN-)") (class "Default")
      (node (ref "C217") (pin "1") (pintype "passive"))
      (node (ref "R154") (pin "2") (pintype "passive"))
      (node (ref "U30") (pin "2") (pinfunction "VIN-_2") (pintype "passive"))
    )
    (net (code "19") (name "Net-(U37-VIN+)") (class "Default")
      (node (ref "C289") (pin "2") (pintype "passive"))
      (node (ref "R186") (pin "2") (pintype "passive"))
      (node (ref "U37") (pin "1") (pinfunction "VIN+_1") (pintype "passive"))
    )
    (net (code "20") (name "Net-(U37-VIN-)") (class "Default")
      (node (ref "C289") (pin "1") (pintype "passive"))
      (node (ref "R190") (pin "2") (pintype "passive"))
      (node (ref "U37") (pin "2") (pinfunction "VIN-_2") (pintype "passive"))
    )
    (net (code "21") (name "VCCA") (class "Default")
      (node (ref "C227") (pin "1") (pintype "passive"))
      (node (ref "C237") (pin "1") (pintype "passive"))
      (node (ref "C257") (pin "1") (pintype "passive"))
      (node (ref "C274") (pin "2") (pintype "passive"))
      (node (ref "C278") (pin "1") (pintype "passive"))
      (node (ref "C283") (pin "1") (pintype "passive"))
      (node (ref "L7") (pin "1") (pinfunction "1_1") (pintype "passive"))
    )
    (net (code "22") (name "VDD_1V2") (class "Default")
      (node (ref "C238") (pin "1") (pintype "passive"))
      (node (ref "C240") (pin "1") (pintype "passive"))
      (node (ref "C253") (pin "1") (pintype "passive"))
      (node (ref "C254") (pin "1") (pintype "passive"))
      (node (ref "C256") (pin "1") (pintype "passive"))
      (node (ref "C354") (pin "1") (pintype "passive"))
      (node (ref "C355") (pin "1") (pintype "passive"))
      (node (ref "C75") (pin "1") (pinfunction "1_1") (pintype "passive"))
      (node (ref "F1") (pin "2") (pinfunction "GND_2") (pintype "passive"))
      (node (ref "L6") (pin "2") (pinfunction "2_2") (pintype "passive"))
    )
    (net (code "23") (name "VDD_1V2_1") (class "Default")
      (node (ref "C71") (pin "2") (pintype "passive"))
      (node (ref "C73") (pin "1") (pintype "passive"))
      (node (ref "R74") (pin "2") (pintype "passive"))
      (node (ref "R76") (pin "1") (pintype "passive"))
      (node (ref "R77") (pin "1") (pintype "passive"))
      (node (ref "U14") (pin "10") (pinfunction "VOUT_10") (pintype "passive"))
      (node (ref "U14") (pin "11") (pinfunction "VOUT_11") (pintype "passive"))
      (node (ref "U14") (pin "5") (pinfunction "VOUT_5") (pintype "passive"))
      (node (ref "U14") (pin "6") (pinfunction "VOUT_6") (pintype "passive"))
      (node (ref "U14") (pin "7") (pinfunction "VOUT_7") (pintype "passive"))
      (node (ref "U14") (pin "8") (pinfunction "VOUT_8") (pintype "passive"))
      (node (ref "U14") (pin "9") (pinfunction "VOUT_9") (pintype "passive"))
    )
    (net (code "24") (name "VDD_1V2_ETH") (class "Default")
      (node (ref "C28") (pin "1") (pintype "passive"))
      (node (ref "U8") (pin "5") (pinfunction "VSENSE_5") (pintype "passive"))
      (node (ref "U8") (pin "7") (pinfunction "VOUT_7") (pintype "passive"))
      (node (ref "U8") (pin "8") (pinfunction "VOUT_8") (pintype "passive"))
    )
    (net (code "25") (name "VDD_1V2_S") (class "Default")
      (node (ref "F1") (pin "1") (pinfunction "1_1") (pintype "passive"))
      (node (ref "R154") (pin "1") (pintype "passive"))
      (node (ref "R77") (pin "2") (pintype "passive"))
    )
    (net (code "26") (name "VDD_1V5") (class "Default")
      (node (ref "C218") (pin "1") (pintype "passive"))
      (node (ref "C226") (pin "1") (pintype "passive"))
      (node (ref "C232") (pin "1") (pintype "passive"))
      (node (ref "C234") (pin "1") (pintype "passive"))
      (node (ref "C246") (pin "1") (pintype "passive"))
      (node (ref "C247") (pin "1") (pintype "passive"))
      (node (ref "C248") (pin "1") (pinfunction "1_1") (pintype "passive"))
      (node (ref "C249") (pin "1") (pintype "passive"))
      (node (ref "C250") (pin "1") (pintype "passive"))
      (node (ref "C262") (pin "1") (pintype "passive"))
      (node (ref "C272") (pin "1") (pintype "passive"))
      (node (ref "C273") (pin "1") (pintype "passive"))
      (node (ref "C282") (pin "1") (pintype "passive"))
      (node (ref "C74") (pin "1") (pintype "passive"))
      (node (ref "C82") (pin "1") (pinfunction "1_1") (pintype "passive"))
      (node (ref "U23") (pin "1") (pinfunction "OUT_1") (pintype "passive"))
      (node (ref "U23") (pin "2") (pinfunction "OUT_2") (pintype "passive"))
      (node (ref "U23") (pin "3") (pinfunction "SENSE/ADJ_3") (pintype "passive"))
    )
    (net (code "27") (name "VDD_1V8") (class "Default")
      (node (ref "C220") (pin "1") (pintype "passive"))
      (node (ref "C221") (pin "1") (pinfunction "1_1") (pintype "passive"))
      (node (ref "C266") (pin "1") (pintype "passive"))
      (node (ref "U31") (pin "5") (pinfunction "OUT_5") (pintype "passive"))
    )
    (net (code "28") (name "VDD_1V8_CLK") (class "Default")
      (node (ref "C321") (pin "1") (pinfunction "1_1") (pintype "passive"))
      (node (ref "U312") (pin "5") (pinfunction "OUT_5") (pintype "passive"))
    )
    (net (code "29") (name "VDD_2V5") (class "Default")
      (node (ref "C235") (pin "1") (pintype "passive"))
      (node (ref "C261") (pin "1") (pintype "passive"))
      (node (ref "C277") (pin "1") (pintype "passive"))
      (node (ref "C79") (pin "1") (pintype "passive"))
      (node (ref "L7") (pin "2") (pinfunction "2_2") (pintype "passive"))
      (node (ref "U24") (pin "1") (pinfunction "OUT_1") (pintype "passive"))
      (node (ref "U24") (pin "2") (pinfunction "OUT_2") (pintype "passive"))
      (node (ref "U24") (pin "3") (pinfunction "SENSE/ADJ_3") (pintype "passive"))
    )
    (net (code "30") (name "VDD_3V3") (class "Default")
      (node (ref "C101") (pin "1") (pintype "passive"))
      (node (ref "C112") (pin "1") (pintype "passive"))
      (node (ref "C214") (pin "1") (pintype "passive"))
      (node (ref "C216") (pin "1") (pintype "passive"))
      (node (ref "C219") (pin "1") (pinfunction "1_1") (pintype "passive"))
      (node (ref "C22") (pin "1") (pintype "passive"))
      (node (ref "C223") (pin "1") (pintype "passive"))
      (node (ref "C228") (pin "1") (pintype "passive"))
      (node (ref "C229") (pin "2") (pintype "passive"))
      (node (ref "C230") (pin "1") (pintype "passive"))
      (node (ref "C242") (pin "1") (pintype "passive"))
      (node (ref "C243") (pin "1") (pintype "passive"))
      (node (ref "C244") (pin "1") (pintype "passive"))
      (node (ref "C258") (pin "1") (pintype "passive"))
      (node (ref "C268") (pin "1") (pintype "passive"))
      (node (ref "C280") (pin "1") (pintype "passive"))
      (node (ref "C286") (pin "1") (pintype "passive"))
      (node (ref "C287") (pin "1") (pintype "passive"))
      (node (ref "C291") (pin "2") (pintype "passive"))
      (node (ref "C292") (pin "1") (pintype "passive"))
      (node (ref "C293") (pin "1") (pintype "passive"))
      (node (ref "C3") (pin "2") (pintype "passive"))
      (node (ref "C322") (pin "1") (pinfunction "1_1") (pintype "passive"))
      (node (ref "C76") (pin "1") (pintype "passive"))
      (node (ref "C77") (pin "1") (pintype "passive"))
      (node (ref "C81") (pin "1") (pintype "passive"))
      (node (ref "C85") (pin "1") (pintype "passive"))
      (node (ref "C86") (pin "1") (pinfunction "1_1") (pintype "passive"))
      (node (ref "C87") (pin "1") (pinfunction "1_1") (pintype "passive"))
      (node (ref "C9") (pin "1") (pinfunction "1_1") (pintype "passive"))
      (node (ref "C94") (pin "1") (pintype "passive"))
      (node (ref "C97") (pin "1") (pintype "passive"))
      (node (ref "F2") (pin "2") (pinfunction "GND_2") (pintype "passive"))
      (node (ref "U23") (pin "6") (pinfunction "SHDN#_6") (pintype "passive"))
      (node (ref "U23") (pin "7") (pinfunction "IN_7") (pintype "passive"))
      (node (ref "U23") (pin "8") (pinfunction "IN_8") (pintype "passive"))
      (node (ref "U24") (pin "6") (pinfunction "SHDN#_6") (pintype "passive"))
      (node (ref "U24") (pin "7") (pinfunction "IN_7") (pintype "passive"))
      (node (ref "U24") (pin "8") (pinfunction "IN_8") (pintype "passive"))
      (node (ref "U30") (pin "4") (pinfunction "VDD_4") (pintype "passive"))
      (node (ref "U31") (pin "1") (pinfunction "IN_1") (pintype "passive"))
      (node (ref "U31") (pin "3") (pinfunction "EN_3") (pintype "input"))
      (node (ref "U312") (pin "1") (pinfunction "IN_1") (pintype "passive"))
      (node (ref "U312") (pin "3") (pinfunction "EN_3") (pintype "input"))
      (node (ref "U37") (pin "4") (pinfunction "VDD_4") (pintype "passive"))
      (node (ref "U37") (pin "8") (pinfunction "A1_8") (pintype "passive"))
    )
    (net (code "31") (name "VDD_3V3_1") (class "Default")
      (node (ref "C80") (pin "2") (pintype "passive"))
      (node (ref "C84") (pin "1") (pintype "passive"))
      (node (ref "R186") (pin "1") (pintype "passive"))
      (node (ref "R85") (pin "2") (pintype "passive"))
      (node (ref "R86") (pin "1") (pintype "passive"))
      (node (ref "U21") (pin "10") (pinfunction "VOUT_10") (pintype "passive"))
      (node (ref "U21") (pin "11") (pinfunction "VOUT_11") (pintype "passive"))
      (node (ref "U21") (pin "5") (pinfunction "VOUT_5") (pintype "passive"))
      (node (ref "U21") (pin "6") (pinfunction "VOUT_6") (pintype "passive"))
      (node (ref "U21") (pin "7") (pinfunction "VOUT_7") (pintype "passive"))
      (node (ref "U21") (pin "8") (pinfunction "VOUT_8") (pintype "passive"))
      (node (ref "U21") (pin "9") (pinfunction "VOUT_9") (pintype "passive"))
    )
    (net (code "32") (name "VDD_3V3_S") (class "Default")
      (node (ref "F2") (pin "1") (pinfunction "1_1") (pintype "passive"))
      (node (ref "R190") (pin "1") (pintype "passive"))
      (node (ref "R86") (pin "2") (pintype "passive"))
    )
    (net (code "33") (name "VDD_5V") (class "Default")
      (node (ref "C107") (pin "1") (pintype "passive"))
      (node (ref "C120") (pin "1") (pinfunction "1_1") (pintype "passive"))
      (node (ref "C23") (pin "1") (pintype "passive"))
      (node (ref "C24") (pin "1") (pintype "passive"))
      (node (ref "C25") (pin "1") (pinfunction "1_1") (pintype "passive"))
      (node (ref "C29") (pin "1") (pintype "passive"))
      (node (ref "C30") (pin "1") (pinfunction "1_1") (pintype "passive"))
      (node (ref "C63") (pin "2") (pintype "passive"))
      (node (ref "C78") (pin "2") (pintype "passive"))
      (node (ref "R1") (pin "2") (pintype "passive"))
      (node (ref "R27") (pin "1") (pintype "passive"))
      (node (ref "R35") (pin "1") (pintype "passive"))
      (node (ref "U14") (pin "19") (pinfunction "PVIN_19") (pintype "passive"))
      (node (ref "U14") (pin "20") (pinfunction "PVIN_20") (pintype "passive"))
      (node (ref "U14") (pin "21") (pinfunction "PVIN_21") (pintype "passive"))
      (node (ref "U14") (pin "33") (pinfunction "AVIN_33") (pintype "passive"))
      (node (ref "U21") (pin "19") (pinfunction "PVIN_19") (pintype "passive"))
      (node (ref "U21") (pin "20") (pinfunction "PVIN_20") (pintype "passive"))
      (node (ref "U21") (pin "21") (pinfunction "PVIN_21") (pintype "passive"))
      (node (ref "U21") (pin "33") (pinfunction "AVIN_33") (pintype "passive"))
      (node (ref "U3") (pin "7") (pinfunction "VOUT_7") (pintype "passive"))
      (node (ref "U8") (pin "14") (pinfunction "PVIN_14") (pintype "passive"))
    )
    (net (code "34") (name "VDD_PLL") (class "Default")
      (node (ref "C279") (pin "2") (pintype "passive"))
      (node (ref "L6") (pin "1") (pinfunction "1_1") (pintype "passive"))
    )
    (net (code "35") (name "VDD_POWER") (class "Default")
      (node (ref "C102") (pin "1") (pinfunction "1_1") (pintype "passive"))
      (node (ref "D7") (pin "2") (pinfunction "CATHODE_2") (pintype "passive"))
      (node (ref "D8") (pin "2") (pinfunction "K_2") (pintype "passive"))
      (node (ref "U3") (pin "1") (pinfunction "VIN_1") (pintype "passive"))
    )
    (net (code "36") (name "VMMC") (class "Default") (node (ref "R82") (pin "1") (pintype "passive")))
    (net (code "37") (name "unconnected-(J2-Pad2)") (class "Default")
      (node (ref "J2") (pin "2") (pinfunction "2_2") (pintype "passive"))
    )
    (net (code "38") (name "unconnected-(U3-EN-Pad3)") (class "Default")
      (node (ref "U3") (pin "3") (pinfunction "EN_3") (pintype "passive+no_connect"))
    )
    (net (code "39") (name "unconnected-(U8-NC(SW)-Pad1)") (class "Default")
      (node (ref "U8") (pin "1") (pinfunction "NC(SW)_1") (pintype "passive+no_connect"))
    )
    (net (code "40") (name "unconnected-(U8-NC(SW)-Pad15)") (class "Default")
      (node (ref "U8") (pin "15") (pinfunction "NC(SW)_15") (pintype "passive+no_connect"))
    )
    (net (code "41") (name "unconnected-(U8-NC(SW)-Pad16)") (class "Default")
      (node (ref "U8") (pin "16") (pinfunction "NC(SW)_16") (pintype "passive+no_connect"))
    )
    (net (code "42") (name "unconnected-(U8-VFB-Pad4)") (class "Default")
      (node (ref "U8") (pin "4") (pinfunction "VFB_4") (pintype "passive+no_connect"))
    )
    (net (code "43") (name "unconnected-(U14-NC(SW)-Pad1)") (class "Default")
      (node (ref "U14") (pin "1") (pinfunction "NC(SW)_1") (pintype "passive+no_connect"))
    )
    (net (code "44") (name "unconnected-(U14-NC(SW)-Pad2)") (class "Default")
      (node (ref "U14") (pin "2") (pinfunction "NC(SW)_2") (pintype "passive+no_connect"))
    )
    (net (code "45") (name "unconnected-(U14-NC(SW)-Pad12)") (class "Default")
      (node (ref "U14") (pin "12") (pinfunction "NC(SW)_12") (pintype "passive+no_connect"))
    )
    (net (code "46") (name "unconnected-(U14-NC(SW)-Pad34)") (class "Default")
      (node (ref "U14") (pin "34") (pinfunction "NC(SW)_34") (pintype "passive+no_connect"))
    )
    (net (code "47") (name "unconnected-(U14-NC(SW)-Pad35)") (class "Default")
      (node (ref "U14") (pin "35") (pinfunction "NC(SW)_35") (pintype "passive+no_connect"))
    )
    (net (code "48") (name "unconnected-(U14-NC(SW)-Pad36)") (class "Default")
      (node (ref "U14") (pin "36") (pinfunction "NC(SW)_36") (pintype "passive+no_connect"))
    )
    (net (code "49") (name "unconnected-(U14-NC(SW)-Pad37)") (class "Default")
      (node (ref "U14") (pin "37") (pinfunction "NC(SW)_37") (pintype "passive+no_connect"))
    )
    (net (code "50") (name "unconnected-(U14-NC(SW)-Pad38)") (class "Default")
      (node (ref "U14") (pin "38") (pinfunction "NC(SW)_38") (pintype "passive+no_connect"))
    )
    (net (code "51") (name "unconnected-(U14-NC-Pad3)") (class "Default")
      (node (ref "U14") (pin "3") (pinfunction "NC_3") (pintype "passive+no_connect"))
    )
    (net (code "52") (name "unconnected-(U14-NC-Pad4)") (class "Default")
      (node (ref "U14") (pin "4") (pinfunction "NC_4") (pintype "passive+no_connect"))
    )
    (net (code "53") (name "unconnected-(U14-NC-Pad22)") (class "Default")
      (node (ref "U14") (pin "22") (pinfunction "NC_22") (pintype "passive+no_connect"))
    )
    (net (code "54") (name "unconnected-(U14-NC-Pad23)") (class "Default")
      (node (ref "U14") (pin "23") (pinfunction "NC_23") (pintype "passive+no_connect"))
    )
    (net (code "55") (name "unconnected-(U14-NC-Pad24)") (class "Default")
      (node (ref "U14") (pin "24") (pinfunction "NC_24") (pintype "passive+no_connect"))
    )
    (net (code "56") (name "unconnected-(U14-NC-Pad25)") (class "Default")
      (node (ref "U14") (pin "25") (pinfunction "NC_25") (pintype "passive+no_connect"))
    )
    (net (code "57") (name "unconnected-(U14-RLLM-Pad29)") (class "Default")
      (node (ref "U14") (pin "29") (pinfunction "RLLM_29") (pintype "passive+no_connect"))
    )
    (net (code "58") (name "unconnected-(U21-NC(SW)-Pad1)") (class "Default")
      (node (ref "U21") (pin "1") (pinfunction "NC(SW)_1") (pintype "passive+no_connect"))
    )
    (net (code "59") (name "unconnected-(U21-NC(SW)-Pad2)") (class "Default")
      (node (ref "U21") (pin "2") (pinfunction "NC(SW)_2") (pintype "passive+no_connect"))
    )
    (net (code "60") (name "unconnected-(U21-NC(SW)-Pad12)") (class "Default")
      (node (ref "U21") (pin "12") (pinfunction "NC(SW)_12") (pintype "passive+no_connect"))
    )
    (net (code "61") (name "unconnected-(U21-NC(SW)-Pad34)") (class "Default")
      (node (ref "U21") (pin "34") (pinfunction "NC(SW)_34") (pintype "passive+no_connect"))
    )
    (net (code "62") (name "unconnected-(U21-NC(SW)-Pad35)") (class "Default")
      (node (ref "U21") (pin "35") (pinfunction "NC(SW)_35") (pintype "passive+no_connect"))
    )
    (net (code "63") (name "unconnected-(U21-NC(SW)-Pad36)") (class "Default")
      (node (ref "U21") (pin "36") (pinfunction "NC(SW)_36") (pintype "passive+no_connect"))
    )
    (net (code "64") (name "unconnected-(U21-NC(SW)-Pad37)") (class "Default")
      (node (ref "U21") (pin "37") (pinfunction "NC(SW)_37") (pintype "passive+no_connect"))
    )
    (net (code "65") (name "unconnected-(U21-NC(SW)-Pad38)") (class "Default")
      (node (ref "U21") (pin "38") (pinfunction "NC(SW)_38") (pintype "passive+no_connect"))
    )
    (net (code "66") (name "unconnected-(U21-NC-Pad3)") (class "Default")
      (node (ref "U21") (pin "3") (pinfunction "NC_3") (pintype "passive+no_connect"))
    )
    (net (code "67") (name "unconnected-(U21-NC-Pad4)") (class "Default")
      (node (ref "U21") (pin "4") (pinfunction "NC_4") (pintype "passive+no_connect"))
    )
    (net (code "68") (name "unconnected-(U21-NC-Pad22)") (class "Default")
      (node (ref "U21") (pin "22") (pinfunction "NC_22") (pintype "passive+no_connect"))
    )
    (net (code "69") (name "unconnected-(U21-NC-Pad23)") (class "Default")
      (node (ref "U21") (pin "23") (pinfunction "NC_23") (pintype "passive+no_connect"))
    )
    (net (code "70") (name "unconnected-(U21-NC-Pad24)") (class "Default")
      (node (ref "U21") (pin "24") (pinfunction "NC_24") (pintype "passive+no_connect"))
    )
    (net (code "71") (name "unconnected-(U21-NC-Pad25)") (class "Default")
      (node (ref "U21") (pin "25") (pinfunction "NC_25") (pintype "passive+no_connect"))
    )
    (net (code "72") (name "unconnected-(U21-RLLM-Pad29)") (class "Default")
      (node (ref "U21") (pin "29") (pinfunction "RLLM_29") (pintype "passive+no_connect"))
    )
    (net (code "73") (name "unconnected-(U31-NR-Pad4)") (class "Default")
      (node (ref "U31") (pin "4") (pinfunction "NR_4") (pintype "passive+no_connect"))
    )
    (net (code "74") (name "unconnected-(U312-NR-Pad4)") (class "Default")
      (node (ref "U312") (pin "4") (pinfunction "NR_4") (pintype "passive+no_connect"))
    )
  )
)
